# 467444_130_3_2-R1.net
KiCad netlist of a schematic drawn in Altium Designer
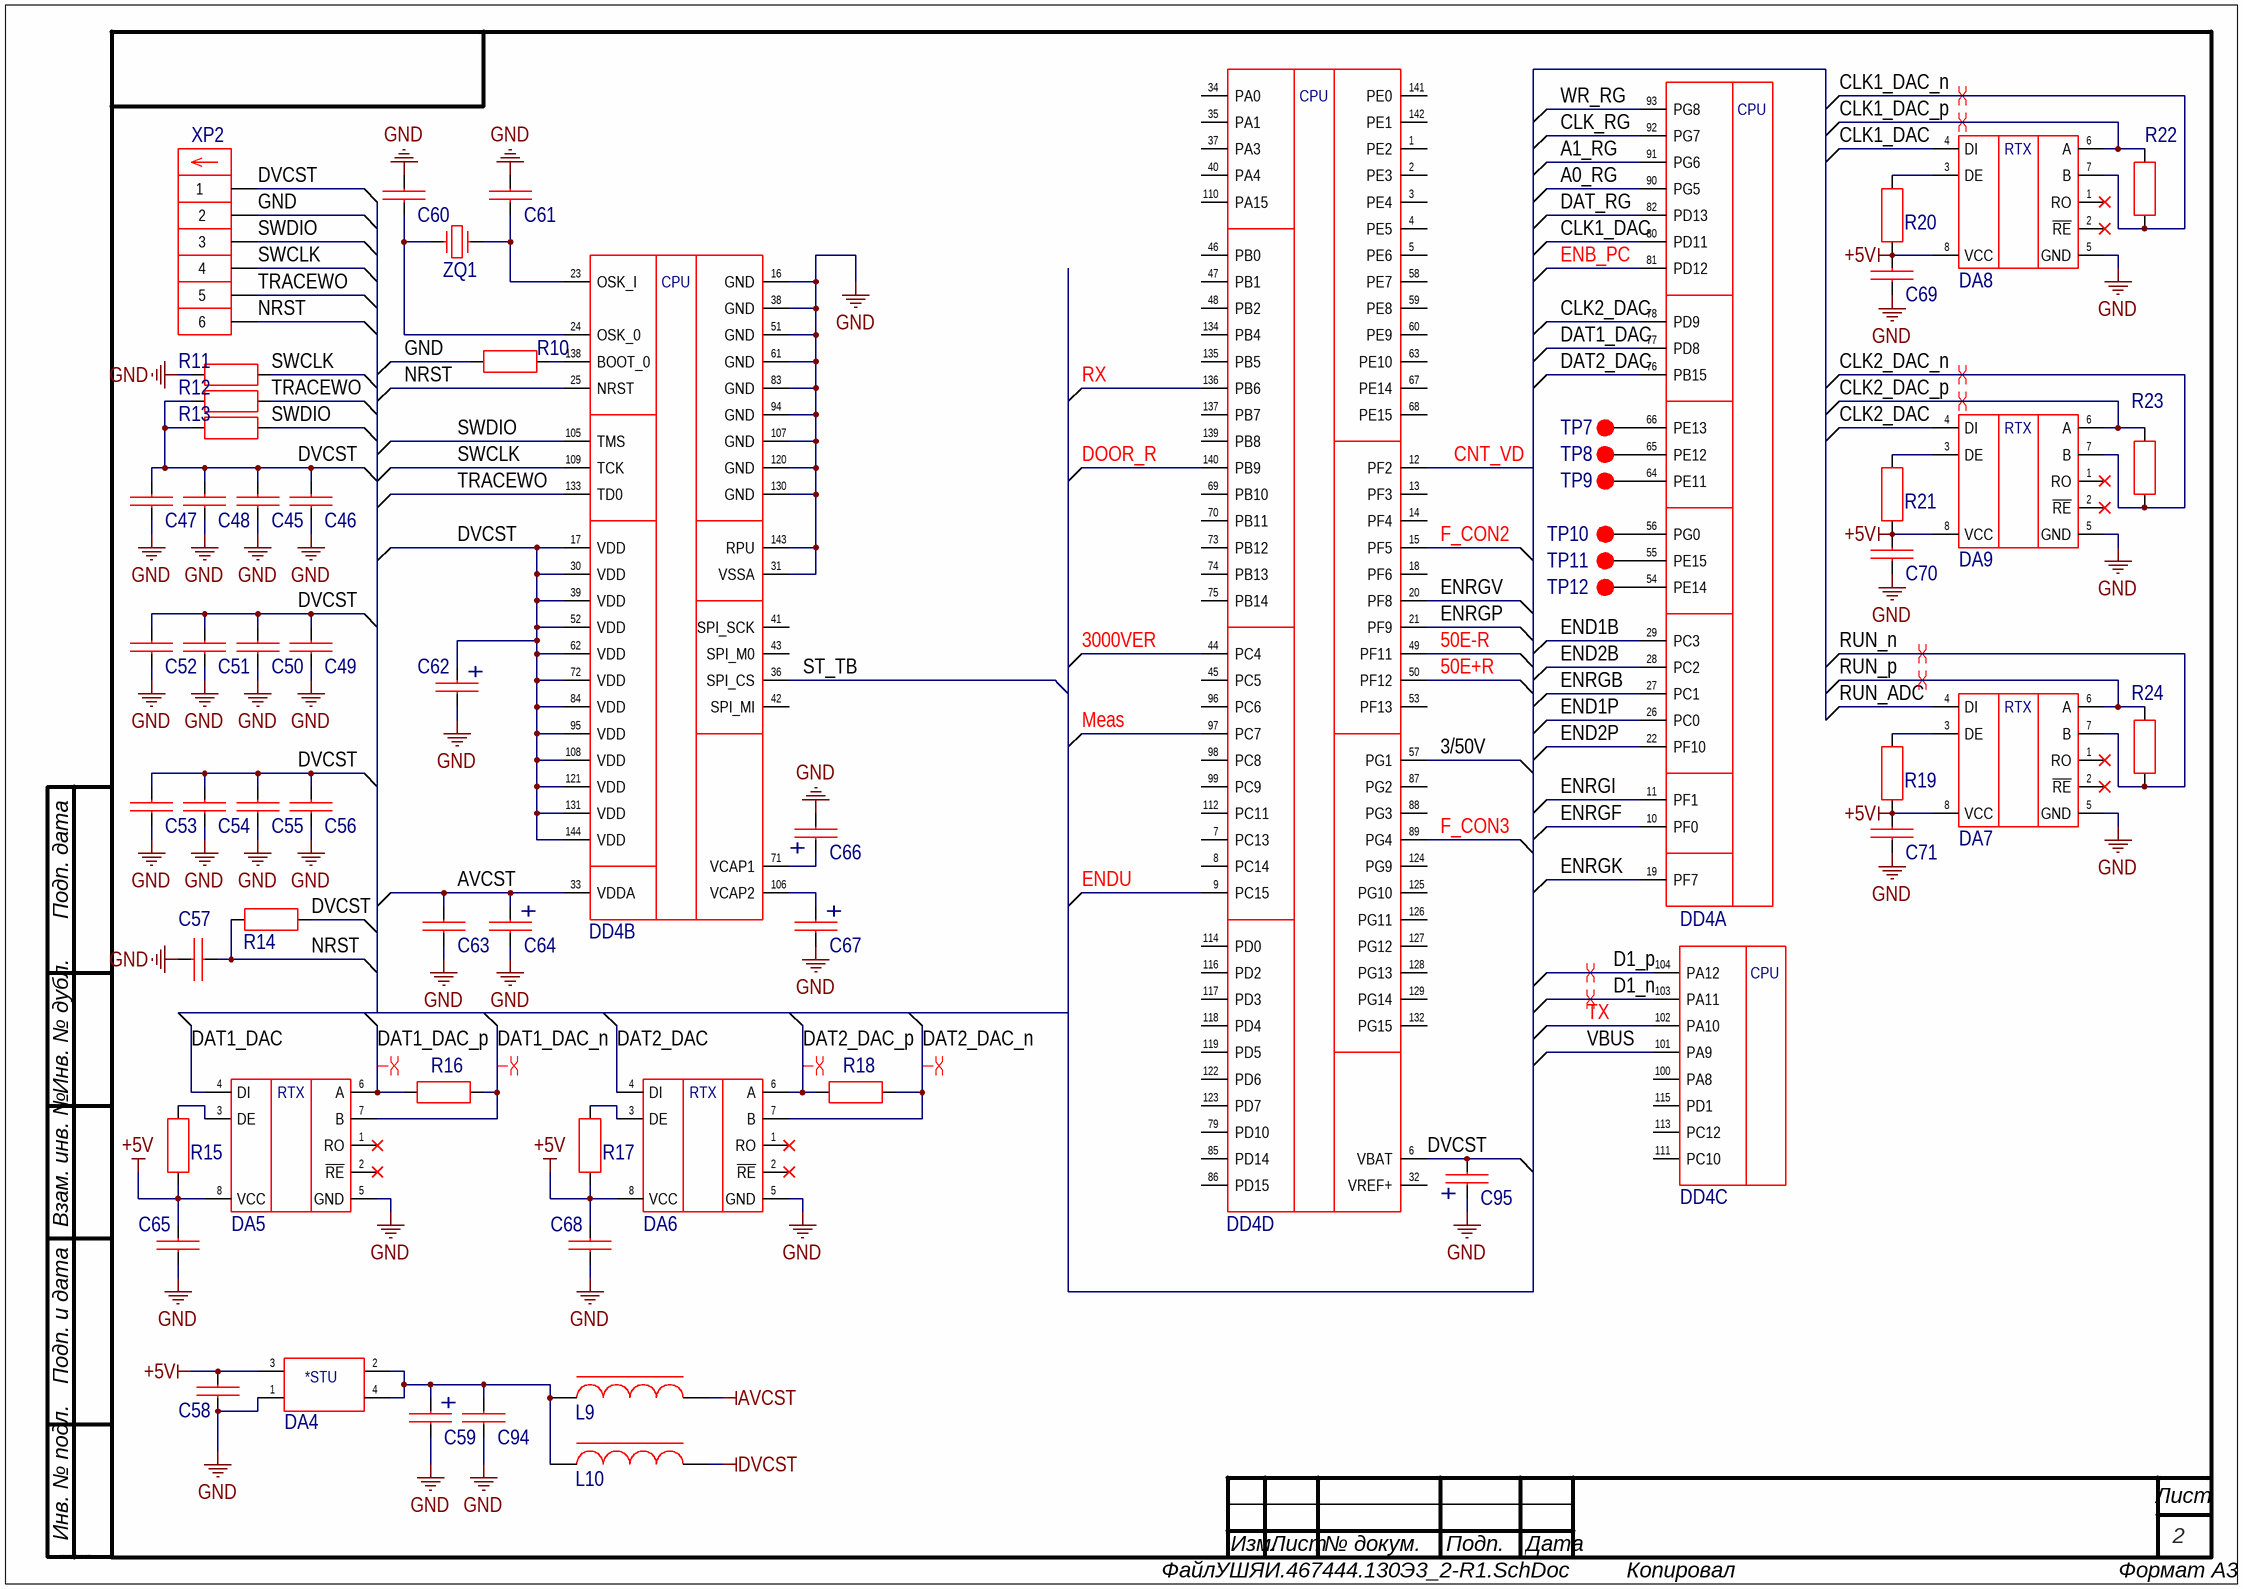
[diagram p0: УШЯИ.467444.130Э3_2-R1.SchDoc]

(export (version "E")
  (design (tool "Eeschema 10.0.6"))
  (components
    (comp (ref "C45")
      (value "0,1 µF")
      (footprint "C_0805 [2012 Metric]")
      (description "Неполярный конденсатор")
      (fields (field (name "MANUFACTURER") "Murata") (field (name "VOLTAGE") "50V"))
      (libsource (lib "lib") (part "C_const"))
    )
    (comp (ref "C46")
      (value "0,1 µF")
      (footprint "C_0805 [2012 Metric]")
      (description "Неполярный конденсатор")
      (fields (field (name "MANUFACTURER") "Murata") (field (name "VOLTAGE") "50V"))
      (libsource (lib "lib") (part "C_const"))
    )
    (comp (ref "C47")
      (value "0,1 µF")
      (footprint "C_0805 [2012 Metric]")
      (description "Неполярный конденсатор")
      (fields (field (name "MANUFACTURER") "Murata") (field (name "VOLTAGE") "50V"))
      (libsource (lib "lib") (part "C_const"))
    )
    (comp (ref "C48")
      (value "0,1 µF")
      (footprint "C_0805 [2012 Metric]")
      (description "Неполярный конденсатор")
      (fields (field (name "MANUFACTURER") "Murata") (field (name "VOLTAGE") "50V"))
      (libsource (lib "lib") (part "C_const"))
    )
    (comp (ref "C49")
      (value "0,1 µF")
      (footprint "C_0805 [2012 Metric]")
      (description "Неполярный конденсатор")
      (fields (field (name "MANUFACTURER") "Murata") (field (name "VOLTAGE") "50V"))
      (libsource (lib "lib") (part "C_const"))
    )
    (comp (ref "C50")
      (value "0,1 µF")
      (footprint "C_0805 [2012 Metric]")
      (description "Неполярный конденсатор")
      (fields (field (name "MANUFACTURER") "Murata") (field (name "VOLTAGE") "50V"))
      (libsource (lib "lib") (part "C_const"))
    )
    (comp (ref "C51")
      (value "0,1 µF")
      (footprint "C_0805 [2012 Metric]")
      (description "Неполярный конденсатор")
      (fields (field (name "MANUFACTURER") "Murata") (field (name "VOLTAGE") "50V"))
      (libsource (lib "lib") (part "C_const"))
    )
    (comp (ref "C52")
      (value "0,1 µF")
      (footprint "C_0805 [2012 Metric]")
      (description "Неполярный конденсатор")
      (fields (field (name "MANUFACTURER") "Murata") (field (name "VOLTAGE") "50V"))
      (libsource (lib "lib") (part "C_const"))
    )
    (comp (ref "C53")
      (value "0,1 µF")
      (footprint "C_0805 [2012 Metric]")
      (description "Неполярный конденсатор")
      (fields (field (name "MANUFACTURER") "Murata") (field (name "VOLTAGE") "50V"))
      (libsource (lib "lib") (part "C_const"))
    )
    (comp (ref "C54")
      (value "0,1 µF")
      (footprint "C_0805 [2012 Metric]")
      (description "Неполярный конденсатор")
      (fields (field (name "MANUFACTURER") "Murata") (field (name "VOLTAGE") "50V"))
      (libsource (lib "lib") (part "C_const"))
    )
    (comp (ref "C55")
      (value "0,1 µF")
      (footprint "C_0805 [2012 Metric]")
      (description "Неполярный конденсатор")
      (fields (field (name "MANUFACTURER") "Murata") (field (name "VOLTAGE") "50V"))
      (libsource (lib "lib") (part "C_const"))
    )
    (comp (ref "C56")
      (value "0,1 µF")
      (footprint "C_0805 [2012 Metric]")
      (description "Неполярный конденсатор")
      (fields (field (name "MANUFACTURER") "Murata") (field (name "VOLTAGE") "50V"))
      (libsource (lib "lib") (part "C_const"))
    )
    (comp (ref "C57")
      (value "0,1 µF")
      (footprint "C_0805 [2012 Metric]")
      (description "Неполярный конденсатор")
      (fields (field (name "MANUFACTURER") "Murata") (field (name "VOLTAGE") "50V"))
      (libsource (lib "lib") (part "C_const"))
    )
    (comp (ref "C58")
      (value "0,1 µF")
      (footprint "C_0805 [2012 Metric]")
      (description "Неполярный конденсатор")
      (fields (field (name "MANUFACTURER") "Murata") (field (name "VOLTAGE") "50V"))
      (libsource (lib "lib") (part "C_const"))
    )
    (comp (ref "C59")
      (value "4,7 µF")
      (footprint "C+_1210 [3528-21 Metric]")
      (description "Полярный конденсатор")
      (fields (field (name "MANUFACTURER") "KYOCERA AVX") (field (name "VOLTAGE") "20V\r\n10V"))
      (libsource (lib "lib") (part "C_electrolytic"))
    )
    (comp (ref "C60")
      (value "20 pF")
      (footprint "C_0805 [2012 Metric]")
      (description "Неполярный конденсатор")
      (fields (field (name "MANUFACTURER") "Murata") (field (name "VOLTAGE") "50V"))
      (libsource (lib "lib") (part "C_const"))
    )
    (comp (ref "C61")
      (value "20 pF")
      (footprint "C_0805 [2012 Metric]")
      (description "Неполярный конденсатор")
      (fields (field (name "MANUFACTURER") "Murata") (field (name "VOLTAGE") "50V"))
      (libsource (lib "lib") (part "C_const"))
    )
    (comp (ref "C62")
      (value "10 µF")
      (footprint "C+_1210 [3528-21 Metric]")
      (description "Полярный конденсатор")
      (fields (field (name "MANUFACTURER") "KYOCERA AVX") (field (name "VOLTAGE") "20V\r\n10V"))
      (libsource (lib "lib") (part "C_electrolytic"))
    )
    (comp (ref "C63")
      (value "0,1 µF")
      (footprint "C_0805 [2012 Metric]")
      (description "Неполярный конденсатор")
      (fields (field (name "MANUFACTURER") "Murata") (field (name "VOLTAGE") "50V"))
      (libsource (lib "lib") (part "C_const"))
    )
    (comp (ref "C64")
      (value "10 µF")
      (footprint "C+_1210 [3528-21 Metric]")
      (description "Полярный конденсатор")
      (fields (field (name "MANUFACTURER") "KYOCERA AVX") (field (name "VOLTAGE") "20V\r\n10V"))
      (libsource (lib "lib") (part "C_electrolytic"))
    )
    (comp (ref "C65")
      (value "0,1 µF")
      (footprint "C_0805 [2012 Metric]")
      (description "Неполярный конденсатор")
      (fields (field (name "MANUFACTURER") "Murata") (field (name "VOLTAGE") "50V"))
      (libsource (lib "lib") (part "C_const"))
    )
    (comp (ref "C66")
      (value "2,2 µF")
      (footprint "C+_1206 [3216-18 Metric]")
      (description "Полярный конденсатор")
      (fields (field (name "MANUFACTURER") "AVX") (field (name "VOLTAGE") "16V\r\n10V"))
      (libsource (lib "lib") (part "C_electrolytic"))
    )
    (comp (ref "C67")
      (value "2,2 µF")
      (footprint "C+_1206 [3216-18 Metric]")
      (description "Полярный конденсатор")
      (fields (field (name "MANUFACTURER") "AVX") (field (name "VOLTAGE") "16V\r\n10V"))
      (libsource (lib "lib") (part "C_electrolytic"))
    )
    (comp (ref "C68")
      (value "0,1 µF")
      (footprint "C_0805 [2012 Metric]")
      (description "Неполярный конденсатор")
      (fields (field (name "MANUFACTURER") "Murata") (field (name "VOLTAGE") "50V"))
      (libsource (lib "lib") (part "C_const"))
    )
    (comp (ref "C69")
      (value "0,1 µF")
      (footprint "C_0805 [2012 Metric]")
      (description "Неполярный конденсатор")
      (fields (field (name "MANUFACTURER") "Murata") (field (name "VOLTAGE") "50V"))
      (libsource (lib "lib") (part "C_const"))
    )
    (comp (ref "C70")
      (value "0,1 µF")
      (footprint "C_0805 [2012 Metric]")
      (description "Неполярный конденсатор")
      (fields (field (name "MANUFACTURER") "Murata") (field (name "VOLTAGE") "50V"))
      (libsource (lib "lib") (part "C_const"))
    )
    (comp (ref "C71")
      (value "0,1 µF")
      (footprint "C_0805 [2012 Metric]")
      (description "Неполярный конденсатор")
      (fields (field (name "MANUFACTURER") "Murata") (field (name "VOLTAGE") "50V"))
      (libsource (lib "lib") (part "C_const"))
    )
    (comp (ref "C94")
      (value "0,1 µF")
      (footprint "C_0805 [2012 Metric]")
      (description "Неполярный конденсатор")
      (fields (field (name "MANUFACTURER") "Murata") (field (name "VOLTAGE") "50V"))
      (libsource (lib "lib") (part "C_const"))
    )
    (comp (ref "C95")
      (value "10 µF")
      (footprint "C+_1210 [3528-21 Metric]")
      (description "Полярный конденсатор")
      (fields (field (name "MANUFACTURER") "KYOCERA AVX") (field (name "VOLTAGE") "20V\r\n10V"))
      (libsource (lib "lib") (part "C_electrolytic"))
    )
    (comp (ref "DA4")
      (value "LD1117AS33TR")
      (footprint "SOT-223")
      (description "IC, Fixed LDO Voltage Regulator, 5.3V to 10V, 1.15V Dropout, 3.3Vout, 1Aout")
      (fields (field (name "MANUFACTURER") "STMicroelectronics"))
      (libsource (lib "lib") (part "VolReg_LD1117AS33TR"))
    )
    (comp (ref "DA5")
      (value "ADM483AR")
      (footprint "SOIC-8_1.27_5x4x1.75")
      (description "IC, Transceiver, RS422/RS485, 1 Driver, 1 Receiver, 4.75 V to 5.25 V, -40°C to 125°C")
      (fields (field (name "MANUFACTURER") "Analog Devices"))
      (libsource (lib "lib") (part "ADM483"))
    )
    (comp (ref "DA6")
      (value "ADM483AR")
      (footprint "SOIC-8_1.27_5x4x1.75")
      (description "IC, Transceiver, RS422/RS485, 1 Driver, 1 Receiver, 4.75 V to 5.25 V, -40°C to 125°C")
      (fields (field (name "MANUFACTURER") "Analog Devices"))
      (libsource (lib "lib") (part "ADM483"))
    )
    (comp (ref "DA7")
      (value "ADM483AR")
      (footprint "SOIC-8_1.27_5x4x1.75")
      (description "IC, Transceiver, RS422/RS485, 1 Driver, 1 Receiver, 4.75 V to 5.25 V, -40°C to 125°C")
      (fields (field (name "MANUFACTURER") "Analog Devices"))
      (libsource (lib "lib") (part "ADM483"))
    )
    (comp (ref "DA8")
      (value "ADM483AR")
      (footprint "SOIC-8_1.27_5x4x1.75")
      (description "IC, Transceiver, RS422/RS485, 1 Driver, 1 Receiver, 4.75 V to 5.25 V, -40°C to 125°C")
      (fields (field (name "MANUFACTURER") "Analog Devices"))
      (libsource (lib "lib") (part "ADM483"))
    )
    (comp (ref "DA9")
      (value "ADM483AR")
      (footprint "SOIC-8_1.27_5x4x1.75")
      (description "IC, Transceiver, RS422/RS485, 1 Driver, 1 Receiver, 4.75 V to 5.25 V, -40°C to 125°C")
      (fields (field (name "MANUFACTURER") "Analog Devices"))
      (libsource (lib "lib") (part "ADM483"))
    )
    (comp (ref "DD4")
      (value "STM32F429VIT6STM32F407ZGTx")
      (footprint "QFP-144[20x20]_0.5_22x22x1.6")
      (description "IC, ARM Cortex-M4, 168 MHz, 1 MB ROM, 192 kB RAM, -40°C to 85°C")
      (fields (field (name "MANUFACTURER") "STMicroelectronics"))
      (libsource (lib "lib") (part "STM32F407"))
    )
    (comp (ref "L9")
      (value "~")
      (footprint "IND_0805 [2012 Metric]")
      (fields (field (name "MANUFACTURER") "Vishay") (field (name "TOLERANCE") "±25%"))
      (libsource (lib "lib") (part "IND_ferromagnetic/ferrite_core"))
    )
    (comp (ref "L10")
      (value "~")
      (footprint "IND_0805 [2012 Metric]")
      (fields (field (name "MANUFACTURER") "Vishay") (field (name "TOLERANCE") "±25%"))
      (libsource (lib "lib") (part "IND_ferromagnetic/ferrite_core"))
    )
    (comp (ref "R10")
      (value "10k")
      (footprint "R_0805 [2012 Metric]")
      (fields (field (name "TOLERANCE") "±5%"))
      (libsource (lib "lib") (part "R_Const"))
    )
    (comp (ref "R11")
      (value "10k")
      (footprint "R_0805 [2012 Metric]")
      (fields (field (name "TOLERANCE") "±5%"))
      (libsource (lib "lib") (part "R_Const"))
    )
    (comp (ref "R12")
      (value "10k")
      (footprint "R_0805 [2012 Metric]")
      (fields (field (name "TOLERANCE") "±5%"))
      (libsource (lib "lib") (part "R_Const"))
    )
    (comp (ref "R13")
      (value "10k")
      (footprint "R_0805 [2012 Metric]")
      (fields (field (name "TOLERANCE") "±5%"))
      (libsource (lib "lib") (part "R_Const"))
    )
    (comp (ref "R14")
      (value "10k")
      (footprint "R_0805 [2012 Metric]")
      (fields (field (name "TOLERANCE") "±5%"))
      (libsource (lib "lib") (part "R_Const"))
    )
    (comp (ref "R15")
      (value "10k")
      (footprint "R_0805 [2012 Metric]")
      (fields (field (name "TOLERANCE") "±5%"))
      (libsource (lib "lib") (part "R_Const"))
    )
    (comp (ref "R16")
      (value "100R")
      (footprint "R_0805 [2012 Metric]")
      (fields (field (name "TOLERANCE") "±5%"))
      (libsource (lib "lib") (part "R_Const"))
    )
    (comp (ref "R17")
      (value "10k")
      (footprint "R_0805 [2012 Metric]")
      (fields (field (name "TOLERANCE") "±5%"))
      (libsource (lib "lib") (part "R_Const"))
    )
    (comp (ref "R18")
      (value "100R")
      (footprint "R_0805 [2012 Metric]")
      (fields (field (name "TOLERANCE") "±5%"))
      (libsource (lib "lib") (part "R_Const"))
    )
    (comp (ref "R19")
      (value "10k")
      (footprint "R_0805 [2012 Metric]")
      (fields (field (name "TOLERANCE") "±5%"))
      (libsource (lib "lib") (part "R_Const"))
    )
    (comp (ref "R20")
      (value "10k")
      (footprint "R_0805 [2012 Metric]")
      (fields (field (name "TOLERANCE") "±5%"))
      (libsource (lib "lib") (part "R_Const"))
    )
    (comp (ref "R21")
      (value "10k")
      (footprint "R_0805 [2012 Metric]")
      (fields (field (name "TOLERANCE") "±5%"))
      (libsource (lib "lib") (part "R_Const"))
    )
    (comp (ref "R22")
      (value "100R")
      (footprint "R_0805 [2012 Metric]")
      (fields (field (name "TOLERANCE") "±5%"))
      (libsource (lib "lib") (part "R_Const"))
    )
    (comp (ref "R23")
      (value "100R")
      (footprint "R_0805 [2012 Metric]")
      (fields (field (name "TOLERANCE") "±5%"))
      (libsource (lib "lib") (part "R_Const"))
    )
    (comp (ref "R24")
      (value "100R")
      (footprint "R_0805 [2012 Metric]")
      (fields (field (name "TOLERANCE") "±5%"))
      (libsource (lib "lib") (part "R_Const"))
    )
    (comp (ref "TP7") (value "~") (footprint "DSP_1.3") (libsource (lib "lib") (part "TP")))
    (comp (ref "TP8") (value "~") (footprint "DSP_1.3") (libsource (lib "lib") (part "TP")))
    (comp (ref "TP9") (value "~") (footprint "DSP_1.3") (libsource (lib "lib") (part "TP")))
    (comp (ref "TP10") (value "~") (footprint "DSP_1.3") (libsource (lib "lib") (part "TP")))
    (comp (ref "TP11") (value "~") (footprint "DSP_1.3") (libsource (lib "lib") (part "TP")))
    (comp (ref "TP12") (value "~") (footprint "DSP_1.3") (libsource (lib "lib") (part "TP")))
    (comp (ref "XP2")
      (value "AMPMODU II 280372-2")
      (footprint "AMP II-280372-2")
      (description "Male, 6 pin, 1 row, Vertical, Board-to-Board, 2.54 mm")
      (fields (field (name "MANUFACTURER") "TE Connectivity"))
      (libsource (lib "lib") (part "M_6"))
    )
    (comp (ref "ZQ1")
      (value "Q 25.0JXS63-12-30/30-FU")
      (footprint "JXS63")
      (fields (field (name "MANUFACTURER") "Jauch Quartz GmbH"))
      (libsource (lib "lib") (part "Rezonator_JXS63"))
    )
  )
  (nets
    (net (code "1") (name "+5V") (class "Default")
      (node (ref "C58") (pin "1") (pinfunction "1_1") (pintype "passive"))
      (node (ref "C65") (pin "2") (pinfunction "2_2") (pintype "passive"))
      (node (ref "C68") (pin "2") (pinfunction "2_2") (pintype "passive"))
      (node (ref "C69") (pin "2") (pinfunction "2_2") (pintype "passive"))
      (node (ref "C70") (pin "2") (pinfunction "2_2") (pintype "passive"))
      (node (ref "C71") (pin "2") (pinfunction "2_2") (pintype "passive"))
      (node (ref "DA4") (pin "3") (pinfunction "VIN_3") (pintype "passive"))
      (node (ref "DA5") (pin "8") (pinfunction "VCC_8") (pintype "passive"))
      (node (ref "DA6") (pin "8") (pinfunction "VCC_8") (pintype "passive"))
      (node (ref "DA7") (pin "8") (pinfunction "VCC_8") (pintype "passive"))
      (node (ref "DA8") (pin "8") (pinfunction "VCC_8") (pintype "passive"))
      (node (ref "DA9") (pin "8") (pinfunction "VCC_8") (pintype "passive"))
      (node (ref "R15") (pin "1") (pinfunction "1_1") (pintype "passive"))
      (node (ref "R17") (pin "1") (pinfunction "1_1") (pintype "passive"))
      (node (ref "R19") (pin "1") (pinfunction "1_1") (pintype "passive"))
      (node (ref "R20") (pin "1") (pinfunction "1_1") (pintype "passive"))
      (node (ref "R21") (pin "1") (pinfunction "1_1") (pintype "passive"))
    )
    (net (code "2") (name "/3{slash}50V") (class "Default")
      (node (ref "DD4") (pin "57") (pinfunction "PG1_57") (pintype "passive"))
    )
    (net (code "3") (name "/50E+R") (class "Default")
      (node (ref "DD4") (pin "50") (pinfunction "PF12_50") (pintype "passive"))
    )
    (net (code "4") (name "/50E-R") (class "Default")
      (node (ref "DD4") (pin "49") (pinfunction "PF11_49") (pintype "passive"))
    )
    (net (code "5") (name "/3000VER") (class "Default")
      (node (ref "DD4") (pin "44") (pinfunction "PC4_44") (pintype "passive"))
    )
    (net (code "6") (name "/A0_RG") (class "Default")
      (node (ref "DD4") (pin "90") (pinfunction "PG5_90") (pintype "passive"))
    )
    (net (code "7") (name "/A1_RG") (class "Default")
      (node (ref "DD4") (pin "91") (pinfunction "PG6_91") (pintype "passive"))
    )
    (net (code "8") (name "/CLK1_DAC") (class "Default")
      (node (ref "DA8") (pin "4") (pinfunction "DI_4") (pintype "passive"))
      (node (ref "DD4") (pin "80") (pinfunction "PD11_80") (pintype "passive"))
    )
    (net (code "9") (name "/CLK1_DAC_n") (class "Default")
      (node (ref "DA8") (pin "7") (pinfunction "B_7") (pintype "passive"))
      (node (ref "R22") (pin "1") (pinfunction "1_1") (pintype "passive"))
    )
    (net (code "10") (name "/CLK1_DAC_p") (class "Default")
      (node (ref "DA8") (pin "6") (pinfunction "A_6") (pintype "passive"))
      (node (ref "R22") (pin "2") (pinfunction "2_2") (pintype "passive"))
    )
    (net (code "11") (name "/CLK2_DAC") (class "Default")
      (node (ref "DA9") (pin "4") (pinfunction "DI_4") (pintype "passive"))
      (node (ref "DD4") (pin "78") (pinfunction "PD9_78") (pintype "passive"))
    )
    (net (code "12") (name "/CLK2_DAC_n") (class "Default")
      (node (ref "DA9") (pin "7") (pinfunction "B_7") (pintype "passive"))
      (node (ref "R23") (pin "1") (pinfunction "1_1") (pintype "passive"))
    )
    (net (code "13") (name "/CLK2_DAC_p") (class "Default")
      (node (ref "DA9") (pin "6") (pinfunction "A_6") (pintype "passive"))
      (node (ref "R23") (pin "2") (pinfunction "2_2") (pintype "passive"))
    )
    (net (code "14") (name "/CLK_RG") (class "Default")
      (node (ref "DD4") (pin "92") (pinfunction "PG7_92") (pintype "passive"))
    )
    (net (code "15") (name "/CNT_VD") (class "Default")
      (node (ref "DD4") (pin "12") (pinfunction "PF2_12") (pintype "passive"))
    )
    (net (code "16") (name "/D1_n") (class "Default")
      (node (ref "DD4") (pin "103") (pinfunction "PA11_103") (pintype "passive"))
    )
    (net (code "17") (name "/D1_p") (class "Default")
      (node (ref "DD4") (pin "104") (pinfunction "PA12_104") (pintype "passive"))
    )
    (net (code "18") (name "/DAT1_DAC") (class "Default")
      (node (ref "DA5") (pin "4") (pinfunction "DI_4") (pintype "passive"))
      (node (ref "DD4") (pin "77") (pinfunction "PD8_77") (pintype "passive"))
    )
    (net (code "19") (name "/DAT1_DAC_n") (class "Default")
      (node (ref "DA5") (pin "7") (pinfunction "B_7") (pintype "passive"))
      (node (ref "R16") (pin "2") (pinfunction "2_2") (pintype "passive"))
    )
    (net (code "20") (name "/DAT1_DAC_p") (class "Default")
      (node (ref "DA5") (pin "6") (pinfunction "A_6") (pintype "passive"))
      (node (ref "R16") (pin "1") (pinfunction "1_1") (pintype "passive"))
    )
    (net (code "21") (name "/DAT2_DAC") (class "Default")
      (node (ref "DA6") (pin "4") (pinfunction "DI_4") (pintype "passive"))
      (node (ref "DD4") (pin "76") (pinfunction "PB15_76") (pintype "passive"))
    )
    (net (code "22") (name "/DAT2_DAC_n") (class "Default")
      (node (ref "DA6") (pin "7") (pinfunction "B_7") (pintype "passive"))
      (node (ref "R18") (pin "2") (pinfunction "2_2") (pintype "passive"))
    )
    (net (code "23") (name "/DAT2_DAC_p") (class "Default")
      (node (ref "DA6") (pin "6") (pinfunction "A_6") (pintype "passive"))
      (node (ref "R18") (pin "1") (pinfunction "1_1") (pintype "passive"))
    )
    (net (code "24") (name "/DAT_RG") (class "Default")
      (node (ref "DD4") (pin "82") (pinfunction "PD13_82") (pintype "passive"))
    )
    (net (code "25") (name "/DOOR_R") (class "Default")
      (node (ref "DD4") (pin "140") (pinfunction "PB9_140") (pintype "passive"))
    )
    (net (code "26") (name "/ENB_PC") (class "Default")
      (node (ref "DD4") (pin "81") (pinfunction "PD12_81") (pintype "passive"))
    )
    (net (code "27") (name "/END1B") (class "Default")
      (node (ref "DD4") (pin "29") (pinfunction "PC3_29") (pintype "passive"))
    )
    (net (code "28") (name "/END1P") (class "Default")
      (node (ref "DD4") (pin "26") (pinfunction "PC0_26") (pintype "passive"))
    )
    (net (code "29") (name "/END2B") (class "Default")
      (node (ref "DD4") (pin "28") (pinfunction "PC2_28") (pintype "passive"))
    )
    (net (code "30") (name "/END2P") (class "Default")
      (node (ref "DD4") (pin "22") (pinfunction "PF10_22") (pintype "passive"))
    )
    (net (code "31") (name "/ENDU") (class "Default")
      (node (ref "DD4") (pin "9") (pinfunction "PC15_9") (pintype "passive"))
    )
    (net (code "32") (name "/ENRGB") (class "Default")
      (node (ref "DD4") (pin "27") (pinfunction "PC1_27") (pintype "passive"))
    )
    (net (code "33") (name "/ENRGF") (class "Default")
      (node (ref "DD4") (pin "10") (pinfunction "PF0_10") (pintype "passive"))
    )
    (net (code "34") (name "/ENRGI") (class "Default")
      (node (ref "DD4") (pin "11") (pinfunction "PF1_11") (pintype "passive"))
    )
    (net (code "35") (name "/ENRGK") (class "Default")
      (node (ref "DD4") (pin "19") (pinfunction "PF7_19") (pintype "passive"))
    )
    (net (code "36") (name "/ENRGP") (class "Default")
      (node (ref "DD4") (pin "21") (pinfunction "PF9_21") (pintype "passive"))
    )
    (net (code "37") (name "/ENRGV") (class "Default")
      (node (ref "DD4") (pin "20") (pinfunction "PF8_20") (pintype "passive"))
    )
    (net (code "38") (name "/F_CON2") (class "Default")
      (node (ref "DD4") (pin "15") (pinfunction "PF5_15") (pintype "passive"))
    )
    (net (code "39") (name "/F_CON3") (class "Default")
      (node (ref "DD4") (pin "89") (pinfunction "PG4_89") (pintype "passive"))
    )
    (net (code "40") (name "/Meas") (class "Default")
      (node (ref "DD4") (pin "97") (pinfunction "PC7_97") (pintype "passive"))
    )
    (net (code "41") (name "/NRST") (class "Default")
      (node (ref "C57") (pin "2") (pinfunction "2_2") (pintype "passive"))
      (node (ref "DD4") (pin "25") (pinfunction "NRST_25") (pintype "passive"))
      (node (ref "R14") (pin "2") (pinfunction "2_2") (pintype "passive"))
      (node (ref "XP2") (pin "6") (pinfunction "6_6") (pintype "passive"))
    )
    (net (code "42") (name "/RUN_ADC") (class "Default")
      (node (ref "DA7") (pin "4") (pinfunction "DI_4") (pintype "passive"))
    )
    (net (code "43") (name "/RUN_n") (class "Default")
      (node (ref "DA7") (pin "7") (pinfunction "B_7") (pintype "passive"))
      (node (ref "R24") (pin "1") (pinfunction "1_1") (pintype "passive"))
    )
    (net (code "44") (name "/RUN_p") (class "Default")
      (node (ref "DA7") (pin "6") (pinfunction "A_6") (pintype "passive"))
      (node (ref "R24") (pin "2") (pinfunction "2_2") (pintype "passive"))
    )
    (net (code "45") (name "/RX") (class "Default")
      (node (ref "DD4") (pin "136") (pinfunction "PB6_136") (pintype "passive"))
    )
    (net (code "46") (name "/ST_TB") (class "Default")
      (node (ref "DD4") (pin "36") (pinfunction "SPI_CS_36") (pintype "passive"))
    )
    (net (code "47") (name "/SWCLK") (class "Default")
      (node (ref "DD4") (pin "109") (pinfunction "TCK_109") (pintype "passive"))
      (node (ref "R11") (pin "2") (pinfunction "2_2") (pintype "passive"))
      (node (ref "XP2") (pin "4") (pinfunction "4_4") (pintype "passive"))
    )
    (net (code "48") (name "/SWDIO") (class "Default")
      (node (ref "DD4") (pin "105") (pinfunction "TMS_105") (pintype "passive"))
      (node (ref "R13") (pin "2") (pinfunction "2_2") (pintype "passive"))
      (node (ref "XP2") (pin "3") (pinfunction "3_3") (pintype "passive"))
    )
    (net (code "49") (name "/TRACEWO") (class "Default")
      (node (ref "DD4") (pin "133") (pinfunction "TD0_133") (pintype "passive"))
      (node (ref "R12") (pin "2") (pinfunction "2_2") (pintype "passive"))
      (node (ref "XP2") (pin "5") (pinfunction "5_5") (pintype "passive"))
    )
    (net (code "50") (name "/TX") (class "Default")
      (node (ref "DD4") (pin "102") (pinfunction "PA10_102") (pintype "passive"))
    )
    (net (code "51") (name "/VBUS") (class "Default")
      (node (ref "DD4") (pin "101") (pinfunction "PA9_101") (pintype "passive"))
    )
    (net (code "52") (name "/WR_RG") (class "Default")
      (node (ref "DD4") (pin "93") (pinfunction "PG8_93") (pintype "passive"))
    )
    (net (code "53") (name "AVCST") (class "Default")
      (node (ref "C63") (pin "2") (pinfunction "2_2") (pintype "passive"))
      (node (ref "C64") (pin "+") (pinfunction "+_+") (pintype "passive"))
      (node (ref "DD4") (pin "33") (pinfunction "VDDA_33") (pintype "passive"))
      (node (ref "L9") (pin "2") (pinfunction "2_2") (pintype "passive"))
    )
    (net (code "54") (name "DVCST") (class "Default")
      (node (ref "C45") (pin "2") (pinfunction "2_2") (pintype "passive"))
      (node (ref "C46") (pin "2") (pinfunction "2_2") (pintype "passive"))
      (node (ref "C47") (pin "2") (pinfunction "2_2") (pintype "passive"))
      (node (ref "C48") (pin "2") (pinfunction "2_2") (pintype "passive"))
      (node (ref "C49") (pin "2") (pinfunction "2_2") (pintype "passive"))
      (node (ref "C50") (pin "2") (pinfunction "2_2") (pintype "passive"))
      (node (ref "C51") (pin "2") (pinfunction "2_2") (pintype "passive"))
      (node (ref "C52") (pin "2") (pinfunction "2_2") (pintype "passive"))
      (node (ref "C53") (pin "2") (pinfunction "2_2") (pintype "passive"))
      (node (ref "C54") (pin "2") (pinfunction "2_2") (pintype "passive"))
      (node (ref "C55") (pin "2") (pinfunction "2_2") (pintype "passive"))
      (node (ref "C56") (pin "2") (pinfunction "2_2") (pintype "passive"))
      (node (ref "C62") (pin "+") (pinfunction "+_+") (pintype "passive"))
      (node (ref "C95") (pin "-") (pinfunction "-_-") (pintype "passive"))
      (node (ref "DD4") (pin "108") (pinfunction "VDD_108") (pintype "passive"))
      (node (ref "DD4") (pin "121") (pinfunction "VDD_121") (pintype "passive"))
      (node (ref "DD4") (pin "131") (pinfunction "VDD_131") (pintype "passive"))
      (node (ref "DD4") (pin "144") (pinfunction "VDD_144") (pintype "passive"))
      (node (ref "DD4") (pin "17") (pinfunction "VDD_17") (pintype "passive"))
      (node (ref "DD4") (pin "30") (pinfunction "VDD_30") (pintype "passive"))
      (node (ref "DD4") (pin "39") (pinfunction "VDD_39") (pintype "passive"))
      (node (ref "DD4") (pin "52") (pinfunction "VDD_52") (pintype "passive"))
      (node (ref "DD4") (pin "6") (pinfunction "VBAT_6") (pintype "passive"))
      (node (ref "DD4") (pin "62") (pinfunction "VDD_62") (pintype "passive"))
      (node (ref "DD4") (pin "72") (pinfunction "VDD_72") (pintype "passive"))
      (node (ref "DD4") (pin "84") (pinfunction "VDD_84") (pintype "passive"))
      (node (ref "DD4") (pin "95") (pinfunction "VDD_95") (pintype "passive"))
      (node (ref "L10") (pin "2") (pinfunction "2_2") (pintype "passive"))
      (node (ref "R12") (pin "1") (pinfunction "1_1") (pintype "passive"))
      (node (ref "R13") (pin "1") (pinfunction "1_1") (pintype "passive"))
      (node (ref "R14") (pin "1") (pinfunction "1_1") (pintype "passive"))
      (node (ref "XP2") (pin "1") (pinfunction "1_1") (pintype "passive"))
    )
    (net (code "55") (name "GND") (class "Default")
      (node (ref "C45") (pin "1") (pinfunction "1_1") (pintype "passive"))
      (node (ref "C46") (pin "1") (pinfunction "1_1") (pintype "passive"))
      (node (ref "C47") (pin "1") (pinfunction "1_1") (pintype "passive"))
      (node (ref "C48") (pin "1") (pinfunction "1_1") (pintype "passive"))
      (node (ref "C49") (pin "1") (pinfunction "1_1") (pintype "passive"))
      (node (ref "C50") (pin "1") (pinfunction "1_1") (pintype "passive"))
      (node (ref "C51") (pin "1") (pinfunction "1_1") (pintype "passive"))
      (node (ref "C52") (pin "1") (pinfunction "1_1") (pintype "passive"))
      (node (ref "C53") (pin "1") (pinfunction "1_1") (pintype "passive"))
      (node (ref "C54") (pin "1") (pinfunction "1_1") (pintype "passive"))
      (node (ref "C55") (pin "1") (pinfunction "1_1") (pintype "passive"))
      (node (ref "C56") (pin "1") (pinfunction "1_1") (pintype "passive"))
      (node (ref "C57") (pin "1") (pinfunction "1_1") (pintype "passive"))
      (node (ref "C58") (pin "2") (pinfunction "2_2") (pintype "passive"))
      (node (ref "C59") (pin "-") (pinfunction "-_-") (pintype "passive"))
      (node (ref "C60") (pin "2") (pinfunction "2_2") (pintype "passive"))
      (node (ref "C61") (pin "2") (pinfunction "2_2") (pintype "passive"))
      (node (ref "C62") (pin "-") (pinfunction "-_-") (pintype "passive"))
      (node (ref "C63") (pin "1") (pinfunction "1_1") (pintype "passive"))
      (node (ref "C64") (pin "-") (pinfunction "-_-") (pintype "passive"))
      (node (ref "C65") (pin "1") (pinfunction "1_1") (pintype "passive"))
      (node (ref "C66") (pin "-") (pinfunction "-_-") (pintype "passive"))
      (node (ref "C67") (pin "-") (pinfunction "-_-") (pintype "passive"))
      (node (ref "C68") (pin "1") (pinfunction "1_1") (pintype "passive"))
      (node (ref "C69") (pin "1") (pinfunction "1_1") (pintype "passive"))
      (node (ref "C70") (pin "1") (pinfunction "1_1") (pintype "passive"))
      (node (ref "C71") (pin "1") (pinfunction "1_1") (pintype "passive"))
      (node (ref "C94") (pin "1") (pinfunction "1_1") (pintype "passive"))
      (node (ref "C95") (pin "+") (pinfunction "+_+") (pintype "passive"))
      (node (ref "DA4") (pin "1") (pinfunction "ADJ/GND_1") (pintype "passive"))
      (node (ref "DA5") (pin "5") (pinfunction "GND_5") (pintype "passive"))
      (node (ref "DA6") (pin "5") (pinfunction "GND_5") (pintype "passive"))
      (node (ref "DA7") (pin "5") (pinfunction "GND_5") (pintype "passive"))
      (node (ref "DA8") (pin "5") (pinfunction "GND_5") (pintype "passive"))
      (node (ref "DA9") (pin "5") (pinfunction "GND_5") (pintype "passive"))
      (node (ref "DD4") (pin "107") (pinfunction "GND_107") (pintype "passive"))
      (node (ref "DD4") (pin "120") (pinfunction "GND_120") (pintype "passive"))
      (node (ref "DD4") (pin "130") (pinfunction "GND_130") (pintype "passive"))
      (node (ref "DD4") (pin "143") (pinfunction "RPU_143") (pintype "passive"))
      (node (ref "DD4") (pin "16") (pinfunction "GND_16") (pintype "passive"))
      (node (ref "DD4") (pin "31") (pinfunction "VSSA_31") (pintype "passive"))
      (node (ref "DD4") (pin "38") (pinfunction "GND_38") (pintype "passive"))
      (node (ref "DD4") (pin "51") (pinfunction "GND_51") (pintype "passive"))
      (node (ref "DD4") (pin "61") (pinfunction "GND_61") (pintype "passive"))
      (node (ref "DD4") (pin "83") (pinfunction "GND_83") (pintype "passive"))
      (node (ref "DD4") (pin "94") (pinfunction "GND_94") (pintype "passive"))
      (node (ref "R10") (pin "1") (pinfunction "1_1") (pintype "passive"))
      (node (ref "R11") (pin "1") (pinfunction "1_1") (pintype "passive"))
      (node (ref "XP2") (pin "2") (pinfunction "2_2") (pintype "passive"))
    )
    (net (code "56") (name "Net-(C59-Pad+)") (class "Default")
      (node (ref "C59") (pin "+") (pinfunction "+_+") (pintype "passive"))
      (node (ref "C94") (pin "2") (pinfunction "2_2") (pintype "passive"))
      (node (ref "DA4") (pin "2") (pinfunction "VOUT_2") (pintype "passive"))
      (node (ref "DA4") (pin "4") (pinfunction "VOUT_4") (pintype "passive"))
      (node (ref "L10") (pin "1") (pinfunction "1_1") (pintype "passive"))
      (node (ref "L9") (pin "1") (pinfunction "1_1") (pintype "passive"))
    )
    (net (code "57") (name "Net-(DA5-DE)") (class "Default")
      (node (ref "DA5") (pin "3") (pinfunction "DE_3") (pintype "passive"))
      (node (ref "R15") (pin "2") (pinfunction "2_2") (pintype "passive"))
    )
    (net (code "58") (name "Net-(DA6-DE)") (class "Default")
      (node (ref "DA6") (pin "3") (pinfunction "DE_3") (pintype "passive"))
      (node (ref "R17") (pin "2") (pinfunction "2_2") (pintype "passive"))
    )
    (net (code "59") (name "Net-(DA7-DE)") (class "Default")
      (node (ref "DA7") (pin "3") (pinfunction "DE_3") (pintype "passive"))
      (node (ref "R19") (pin "2") (pinfunction "2_2") (pintype "passive"))
    )
    (net (code "60") (name "Net-(DA8-DE)") (class "Default")
      (node (ref "DA8") (pin "3") (pinfunction "DE_3") (pintype "passive"))
      (node (ref "R20") (pin "2") (pinfunction "2_2") (pintype "passive"))
    )
    (net (code "61") (name "Net-(DA9-DE)") (class "Default")
      (node (ref "DA9") (pin "3") (pinfunction "DE_3") (pintype "passive"))
      (node (ref "R21") (pin "2") (pinfunction "2_2") (pintype "passive"))
    )
    (net (code "62") (name "Net-(DD4A-PE11)") (class "Default")
      (node (ref "DD4") (pin "64") (pinfunction "PE11_64") (pintype "passive"))
      (node (ref "TP9") (pin "1") (pinfunction "1_1") (pintype "passive"))
    )
    (net (code "63") (name "Net-(DD4A-PE12)") (class "Default")
      (node (ref "DD4") (pin "65") (pinfunction "PE12_65") (pintype "passive"))
      (node (ref "TP8") (pin "1") (pinfunction "1_1") (pintype "passive"))
    )
    (net (code "64") (name "Net-(DD4A-PE13)") (class "Default")
      (node (ref "DD4") (pin "66") (pinfunction "PE13_66") (pintype "passive"))
      (node (ref "TP7") (pin "1") (pinfunction "1_1") (pintype "passive"))
    )
    (net (code "65") (name "Net-(DD4A-PE14)") (class "Default")
      (node (ref "DD4") (pin "54") (pinfunction "PE14_54") (pintype "passive"))
      (node (ref "TP12") (pin "1") (pinfunction "1_1") (pintype "passive"))
    )
    (net (code "66") (name "Net-(DD4A-PE15)") (class "Default")
      (node (ref "DD4") (pin "55") (pinfunction "PE15_55") (pintype "passive"))
      (node (ref "TP11") (pin "1") (pinfunction "1_1") (pintype "passive"))
    )
    (net (code "67") (name "Net-(DD4A-PG0)") (class "Default")
      (node (ref "DD4") (pin "56") (pinfunction "PG0_56") (pintype "passive"))
      (node (ref "TP10") (pin "1") (pinfunction "1_1") (pintype "passive"))
    )
    (net (code "68") (name "Net-(DD4B-BOOT_0)") (class "Default")
      (node (ref "DD4") (pin "138") (pinfunction "BOOT_0_138") (pintype "passive"))
      (node (ref "R10") (pin "2") (pinfunction "2_2") (pintype "passive"))
    )
    (net (code "69") (name "Net-(DD4B-OSK_0)") (class "Default")
      (node (ref "C60") (pin "1") (pinfunction "1_1") (pintype "passive"))
      (node (ref "DD4") (pin "24") (pinfunction "OSK_0_24") (pintype "passive"))
      (node (ref "ZQ1") (pin "1") (pinfunction "1_1") (pintype "passive"))
    )
    (net (code "70") (name "Net-(DD4B-OSK_I)") (class "Default")
      (node (ref "C61") (pin "1") (pinfunction "1_1") (pintype "passive"))
      (node (ref "DD4") (pin "23") (pinfunction "OSK_I_23") (pintype "passive"))
      (node (ref "ZQ1") (pin "3") (pinfunction "3_3") (pintype "passive"))
    )
    (net (code "71") (name "Net-(DD4B-VCAP1)") (class "Default")
      (node (ref "C66") (pin "+") (pinfunction "+_+") (pintype "passive"))
      (node (ref "DD4") (pin "71") (pinfunction "VCAP1_71") (pintype "passive"))
    )
    (net (code "72") (name "Net-(DD4B-VCAP2)") (class "Default")
      (node (ref "C67") (pin "+") (pinfunction "+_+") (pintype "passive"))
      (node (ref "DD4") (pin "106") (pinfunction "VCAP2_106") (pintype "passive"))
    )
    (net (code "73") (name "unconnected-(DA5-RO-Pad1)") (class "Default")
      (node (ref "DA5") (pin "1") (pinfunction "RO_1") (pintype "passive+no_connect"))
    )
    (net (code "74") (name "unconnected-(DA5-~{RE}-Pad2)") (class "Default")
      (node (ref "DA5") (pin "2") (pinfunction "~{RE}_2") (pintype "passive+no_connect"))
    )
    (net (code "75") (name "unconnected-(DA6-RO-Pad1)") (class "Default")
      (node (ref "DA6") (pin "1") (pinfunction "RO_1") (pintype "passive+no_connect"))
    )
    (net (code "76") (name "unconnected-(DA6-~{RE}-Pad2)") (class "Default")
      (node (ref "DA6") (pin "2") (pinfunction "~{RE}_2") (pintype "passive+no_connect"))
    )
    (net (code "77") (name "unconnected-(DA7-RO-Pad1)") (class "Default")
      (node (ref "DA7") (pin "1") (pinfunction "RO_1") (pintype "passive+no_connect"))
    )
    (net (code "78") (name "unconnected-(DA7-~{RE}-Pad2)") (class "Default")
      (node (ref "DA7") (pin "2") (pinfunction "~{RE}_2") (pintype "passive+no_connect"))
    )
    (net (code "79") (name "unconnected-(DA8-RO-Pad1)") (class "Default")
      (node (ref "DA8") (pin "1") (pinfunction "RO_1") (pintype "passive+no_connect"))
    )
    (net (code "80") (name "unconnected-(DA8-~{RE}-Pad2)") (class "Default")
      (node (ref "DA8") (pin "2") (pinfunction "~{RE}_2") (pintype "passive+no_connect"))
    )
    (net (code "81") (name "unconnected-(DA9-RO-Pad1)") (class "Default")
      (node (ref "DA9") (pin "1") (pinfunction "RO_1") (pintype "passive+no_connect"))
    )
    (net (code "82") (name "unconnected-(DA9-~{RE}-Pad2)") (class "Default")
      (node (ref "DA9") (pin "2") (pinfunction "~{RE}_2") (pintype "passive+no_connect"))
    )
    (net (code "83") (name "unconnected-(DD4B-SPI_M0-Pad43)") (class "Default")
      (node (ref "DD4") (pin "43") (pinfunction "SPI_M0_43") (pintype "passive"))
    )
    (net (code "84") (name "unconnected-(DD4B-SPI_MI-Pad42)") (class "Default")
      (node (ref "DD4") (pin "42") (pinfunction "SPI_MI_42") (pintype "passive"))
    )
    (net (code "85") (name "unconnected-(DD4B-SPI_SCK-Pad41)") (class "Default")
      (node (ref "DD4") (pin "41") (pinfunction "SPI_SCK_41") (pintype "passive"))
    )
    (net (code "86") (name "unconnected-(DD4C-PA8-Pad100)") (class "Default")
      (node (ref "DD4") (pin "100") (pinfunction "PA8_100") (pintype "passive"))
    )
    (net (code "87") (name "unconnected-(DD4C-PC10-Pad111)") (class "Default")
      (node (ref "DD4") (pin "111") (pinfunction "PC10_111") (pintype "passive"))
    )
    (net (code "88") (name "unconnected-(DD4C-PC12-Pad113)") (class "Default")
      (node (ref "DD4") (pin "113") (pinfunction "PC12_113") (pintype "passive"))
    )
    (net (code "89") (name "unconnected-(DD4C-PD1-Pad115)") (class "Default")
      (node (ref "DD4") (pin "115") (pinfunction "PD1_115") (pintype "passive"))
    )
    (net (code "90") (name "unconnected-(DD4D-PA0-Pad34)") (class "Default")
      (node (ref "DD4") (pin "34") (pinfunction "PA0_34") (pintype "passive"))
    )
    (net (code "91") (name "unconnected-(DD4D-PA1-Pad35)") (class "Default")
      (node (ref "DD4") (pin "35") (pinfunction "PA1_35") (pintype "passive"))
    )
    (net (code "92") (name "unconnected-(DD4D-PA3-Pad37)") (class "Default")
      (node (ref "DD4") (pin "37") (pinfunction "PA3_37") (pintype "passive"))
    )
    (net (code "93") (name "unconnected-(DD4D-PA4-Pad40)") (class "Default")
      (node (ref "DD4") (pin "40") (pinfunction "PA4_40") (pintype "passive"))
    )
    (net (code "94") (name "unconnected-(DD4D-PA15-Pad110)") (class "Default")
      (node (ref "DD4") (pin "110") (pinfunction "PA15_110") (pintype "passive"))
    )
    (net (code "95") (name "unconnected-(DD4D-PB0-Pad46)") (class "Default")
      (node (ref "DD4") (pin "46") (pinfunction "PB0_46") (pintype "passive"))
    )
    (net (code "96") (name "unconnected-(DD4D-PB1-Pad47)") (class "Default")
      (node (ref "DD4") (pin "47") (pinfunction "PB1_47") (pintype "passive"))
    )
    (net (code "97") (name "unconnected-(DD4D-PB2-Pad48)") (class "Default")
      (node (ref "DD4") (pin "48") (pinfunction "PB2_48") (pintype "passive"))
    )
    (net (code "98") (name "unconnected-(DD4D-PB4-Pad134)") (class "Default")
      (node (ref "DD4") (pin "134") (pinfunction "PB4_134") (pintype "passive"))
    )
    (net (code "99") (name "unconnected-(DD4D-PB5-Pad135)") (class "Default")
      (node (ref "DD4") (pin "135") (pinfunction "PB5_135") (pintype "passive"))
    )
    (net (code "100") (name "unconnected-(DD4D-PB7-Pad137)") (class "Default")
      (node (ref "DD4") (pin "137") (pinfunction "PB7_137") (pintype "passive"))
    )
    (net (code "101") (name "unconnected-(DD4D-PB8-Pad139)") (class "Default")
      (node (ref "DD4") (pin "139") (pinfunction "PB8_139") (pintype "passive"))
    )
    (net (code "102") (name "unconnected-(DD4D-PB10-Pad69)") (class "Default")
      (node (ref "DD4") (pin "69") (pinfunction "PB10_69") (pintype "passive"))
    )
    (net (code "103") (name "unconnected-(DD4D-PB11-Pad70)") (class "Default")
      (node (ref "DD4") (pin "70") (pinfunction "PB11_70") (pintype "passive"))
    )
    (net (code "104") (name "unconnected-(DD4D-PB12-Pad73)") (class "Default")
      (node (ref "DD4") (pin "73") (pinfunction "PB12_73") (pintype "passive"))
    )
    (net (code "105") (name "unconnected-(DD4D-PB13-Pad74)") (class "Default")
      (node (ref "DD4") (pin "74") (pinfunction "PB13_74") (pintype "passive"))
    )
    (net (code "106") (name "unconnected-(DD4D-PB14-Pad75)") (class "Default")
      (node (ref "DD4") (pin "75") (pinfunction "PB14_75") (pintype "passive"))
    )
    (net (code "107") (name "unconnected-(DD4D-PC5-Pad45)") (class "Default")
      (node (ref "DD4") (pin "45") (pinfunction "PC5_45") (pintype "passive"))
    )
    (net (code "108") (name "unconnected-(DD4D-PC6-Pad96)") (class "Default")
      (node (ref "DD4") (pin "96") (pinfunction "PC6_96") (pintype "passive"))
    )
    (net (code "109") (name "unconnected-(DD4D-PC8-Pad98)") (class "Default")
      (node (ref "DD4") (pin "98") (pinfunction "PC8_98") (pintype "passive"))
    )
    (net (code "110") (name "unconnected-(DD4D-PC9-Pad99)") (class "Default")
      (node (ref "DD4") (pin "99") (pinfunction "PC9_99") (pintype "passive"))
    )
    (net (code "111") (name "unconnected-(DD4D-PC11-Pad112)") (class "Default")
      (node (ref "DD4") (pin "112") (pinfunction "PC11_112") (pintype "passive"))
    )
    (net (code "112") (name "unconnected-(DD4D-PC13-Pad7)") (class "Default")
      (node (ref "DD4") (pin "7") (pinfunction "PC13_7") (pintype "passive"))
    )
    (net (code "113") (name "unconnected-(DD4D-PC14-Pad8)") (class "Default")
      (node (ref "DD4") (pin "8") (pinfunction "PC14_8") (pintype "passive"))
    )
    (net (code "114") (name "unconnected-(DD4D-PD0-Pad114)") (class "Default")
      (node (ref "DD4") (pin "114") (pinfunction "PD0_114") (pintype "passive"))
    )
    (net (code "115") (name "unconnected-(DD4D-PD2-Pad116)") (class "Default")
      (node (ref "DD4") (pin "116") (pinfunction "PD2_116") (pintype "passive"))
    )
    (net (code "116") (name "unconnected-(DD4D-PD3-Pad117)") (class "Default")
      (node (ref "DD4") (pin "117") (pinfunction "PD3_117") (pintype "passive"))
    )
    (net (code "117") (name "unconnected-(DD4D-PD4-Pad118)") (class "Default")
      (node (ref "DD4") (pin "118") (pinfunction "PD4_118") (pintype "passive"))
    )
    (net (code "118") (name "unconnected-(DD4D-PD5-Pad119)") (class "Default")
      (node (ref "DD4") (pin "119") (pinfunction "PD5_119") (pintype "passive"))
    )
    (net (code "119") (name "unconnected-(DD4D-PD6-Pad122)") (class "Default")
      (node (ref "DD4") (pin "122") (pinfunction "PD6_122") (pintype "passive"))
    )
    (net (code "120") (name "unconnected-(DD4D-PD7-Pad123)") (class "Default")
      (node (ref "DD4") (pin "123") (pinfunction "PD7_123") (pintype "passive"))
    )
    (net (code "121") (name "unconnected-(DD4D-PD10-Pad79)") (class "Default")
      (node (ref "DD4") (pin "79") (pinfunction "PD10_79") (pintype "passive"))
    )
    (net (code "122") (name "unconnected-(DD4D-PD14-Pad85)") (class "Default")
      (node (ref "DD4") (pin "85") (pinfunction "PD14_85") (pintype "passive"))
    )
    (net (code "123") (name "unconnected-(DD4D-PD15-Pad86)") (class "Default")
      (node (ref "DD4") (pin "86") (pinfunction "PD15_86") (pintype "passive"))
    )
    (net (code "124") (name "unconnected-(DD4D-PE0-Pad141)") (class "Default")
      (node (ref "DD4") (pin "141") (pinfunction "PE0_141") (pintype "passive"))
    )
    (net (code "125") (name "unconnected-(DD4D-PE1-Pad142)") (class "Default")
      (node (ref "DD4") (pin "142") (pinfunction "PE1_142") (pintype "passive"))
    )
    (net (code "126") (name "unconnected-(DD4D-PE2-Pad1)") (class "Default")
      (node (ref "DD4") (pin "1") (pinfunction "PE2_1") (pintype "passive"))
    )
    (net (code "127") (name "unconnected-(DD4D-PE3-Pad2)") (class "Default")
      (node (ref "DD4") (pin "2") (pinfunction "PE3_2") (pintype "passive"))
    )
    (net (code "128") (name "unconnected-(DD4D-PE4-Pad3)") (class "Default")
      (node (ref "DD4") (pin "3") (pinfunction "PE4_3") (pintype "passive"))
    )
    (net (code "129") (name "unconnected-(DD4D-PE5-Pad4)") (class "Default")
      (node (ref "DD4") (pin "4") (pinfunction "PE5_4") (pintype "passive"))
    )
    (net (code "130") (name "unconnected-(DD4D-PE6-Pad5)") (class "Default")
      (node (ref "DD4") (pin "5") (pinfunction "PE6_5") (pintype "passive"))
    )
    (net (code "131") (name "unconnected-(DD4D-PE7-Pad58)") (class "Default")
      (node (ref "DD4") (pin "58") (pinfunction "PE7_58") (pintype "passive"))
    )
    (net (code "132") (name "unconnected-(DD4D-PE8-Pad59)") (class "Default")
      (node (ref "DD4") (pin "59") (pinfunction "PE8_59") (pintype "passive"))
    )
    (net (code "133") (name "unconnected-(DD4D-PE9-Pad60)") (class "Default")
      (node (ref "DD4") (pin "60") (pinfunction "PE9_60") (pintype "passive"))
    )
    (net (code "134") (name "unconnected-(DD4D-PE10-Pad63)") (class "Default")
      (node (ref "DD4") (pin "63") (pinfunction "PE10_63") (pintype "passive"))
    )
    (net (code "135") (name "unconnected-(DD4D-PE14-Pad67)") (class "Default")
      (node (ref "DD4") (pin "67") (pinfunction "PE14_67") (pintype "passive"))
    )
    (net (code "136") (name "unconnected-(DD4D-PE15-Pad68)") (class "Default")
      (node (ref "DD4") (pin "68") (pinfunction "PE15_68") (pintype "passive"))
    )
    (net (code "137") (name "unconnected-(DD4D-PF3-Pad13)") (class "Default")
      (node (ref "DD4") (pin "13") (pinfunction "PF3_13") (pintype "passive"))
    )
    (net (code "138") (name "unconnected-(DD4D-PF4-Pad14)") (class "Default")
      (node (ref "DD4") (pin "14") (pinfunction "PF4_14") (pintype "passive"))
    )
    (net (code "139") (name "unconnected-(DD4D-PF6-Pad18)") (class "Default")
      (node (ref "DD4") (pin "18") (pinfunction "PF6_18") (pintype "passive"))
    )
    (net (code "140") (name "unconnected-(DD4D-PF13-Pad53)") (class "Default")
      (node (ref "DD4") (pin "53") (pinfunction "PF13_53") (pintype "passive"))
    )
    (net (code "141") (name "unconnected-(DD4D-PG2-Pad87)") (class "Default")
      (node (ref "DD4") (pin "87") (pinfunction "PG2_87") (pintype "passive"))
    )
    (net (code "142") (name "unconnected-(DD4D-PG3-Pad88)") (class "Default")
      (node (ref "DD4") (pin "88") (pinfunction "PG3_88") (pintype "passive"))
    )
    (net (code "143") (name "unconnected-(DD4D-PG9-Pad124)") (class "Default")
      (node (ref "DD4") (pin "124") (pinfunction "PG9_124") (pintype "passive"))
    )
    (net (code "144") (name "unconnected-(DD4D-PG10-Pad125)") (class "Default")
      (node (ref "DD4") (pin "125") (pinfunction "PG10_125") (pintype "passive"))
    )
    (net (code "145") (name "unconnected-(DD4D-PG11-Pad126)") (class "Default")
      (node (ref "DD4") (pin "126") (pinfunction "PG11_126") (pintype "passive"))
    )
    (net (code "146") (name "unconnected-(DD4D-PG12-Pad127)") (class "Default")
      (node (ref "DD4") (pin "127") (pinfunction "PG12_127") (pintype "passive"))
    )
    (net (code "147") (name "unconnected-(DD4D-PG13-Pad128)") (class "Default")
      (node (ref "DD4") (pin "128") (pinfunction "PG13_128") (pintype "passive"))
    )
    (net (code "148") (name "unconnected-(DD4D-PG14-Pad129)") (class "Default")
      (node (ref "DD4") (pin "129") (pinfunction "PG14_129") (pintype "passive"))
    )
    (net (code "149") (name "unconnected-(DD4D-PG15-Pad132)") (class "Default")
      (node (ref "DD4") (pin "132") (pinfunction "PG15_132") (pintype "passive"))
    )
    (net (code "150") (name "unconnected-(DD4D-VREF+-Pad32)") (class "Default")
      (node (ref "DD4") (pin "32") (pinfunction "VREF+_32") (pintype "passive"))
    )
  )
)
